# mother_v1.net
KiCad netlist of a schematic drawn in EAGLE
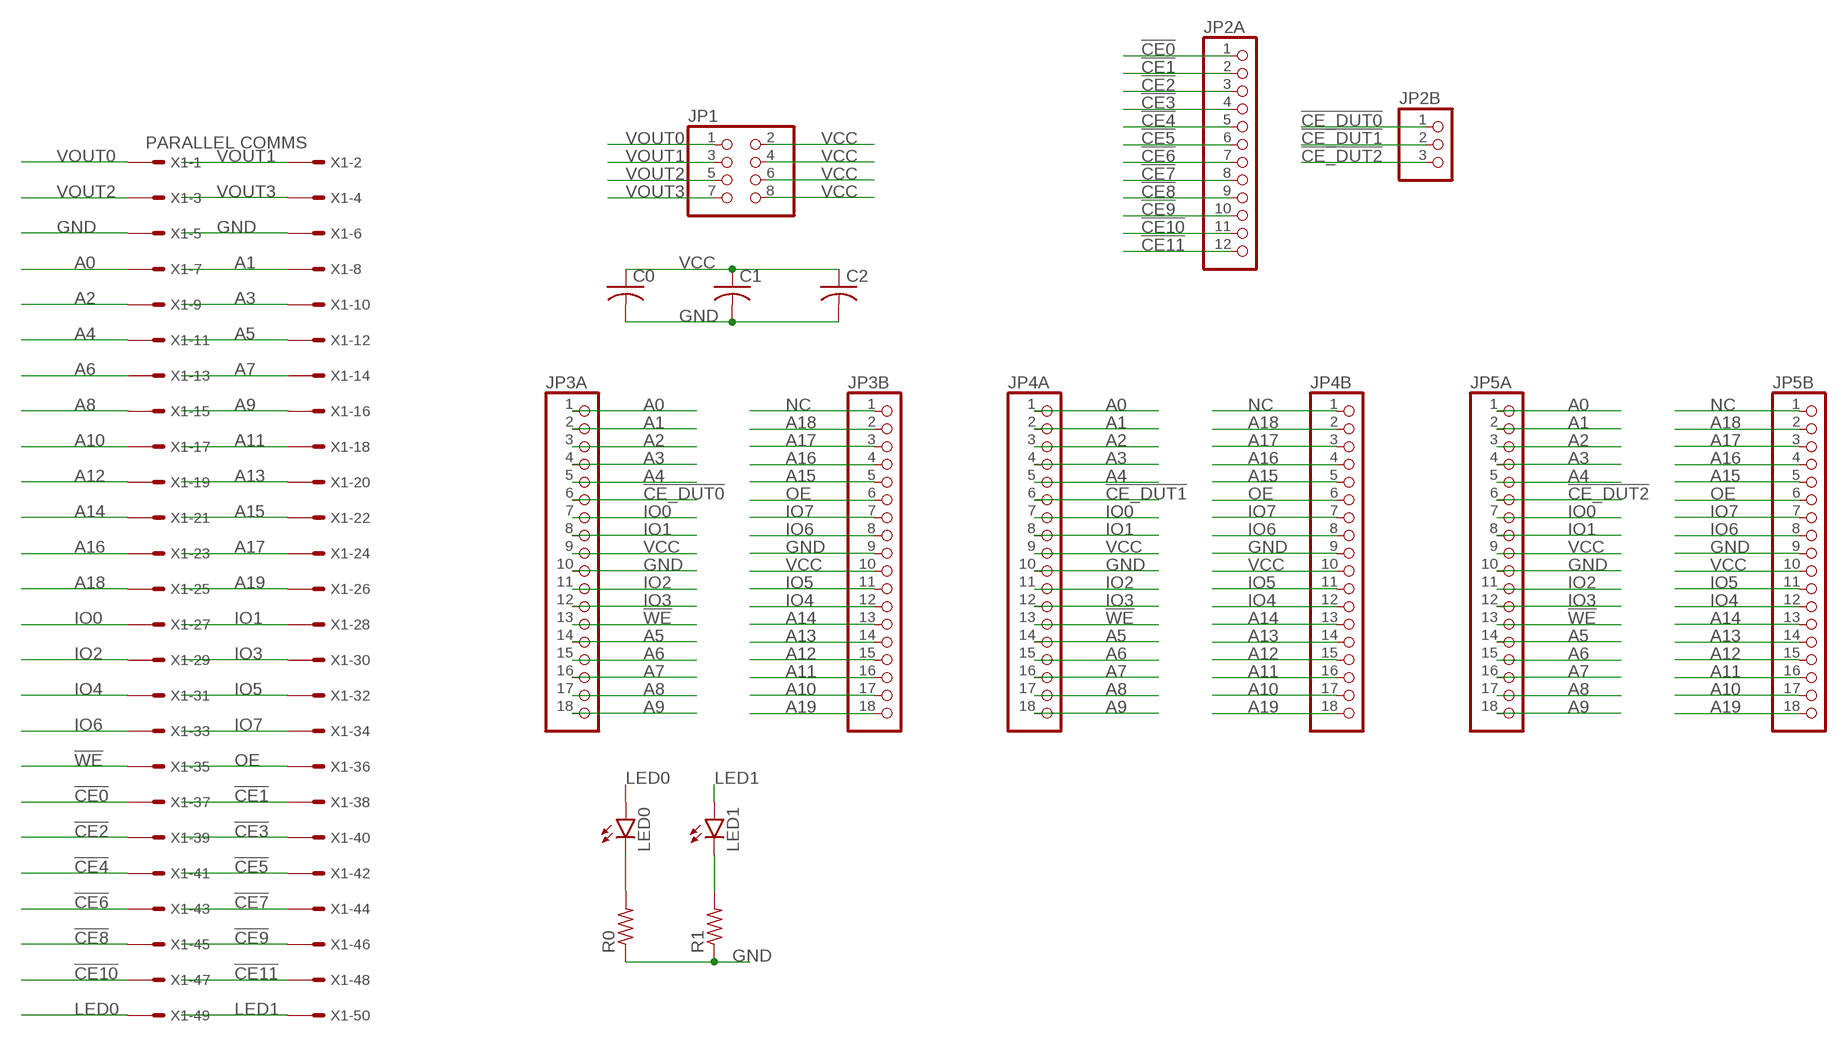
[diagram p0: schematic, sheet 1]

(export (version "E")
  (design (tool "Eeschema 10.0.6"))
  (components
    (comp (ref "C0")
      (value "C-USC0805")
      (footprint "eagle-import:C0805")
      (libsource (lib "eagle-import") (part "C-USC0805"))
    )
    (comp (ref "C1")
      (value "C-USC0805")
      (footprint "eagle-import:C0805")
      (libsource (lib "eagle-import") (part "C-USC0805"))
    )
    (comp (ref "C2")
      (value "C-USC0805")
      (footprint "eagle-import:C0805")
      (libsource (lib "eagle-import") (part "C-USC0805"))
    )
    (comp (ref "JP1")
      (value "PINHD-2X4")
      (footprint "eagle-import:2X04")
      (libsource (lib "eagle-import") (part "PINHD-2X4"))
    )
    (comp (ref "JP2A")
      (value "PINHD-1X12")
      (footprint "eagle-import:1X12")
      (libsource (lib "eagle-import") (part "PINHD-1X12"))
    )
    (comp (ref "JP2B")
      (value "PINHD-1X3")
      (footprint "eagle-import:1X03")
      (libsource (lib "eagle-import") (part "PINHD-1X3"))
    )
    (comp (ref "JP3A")
      (value "PINHD-1X18")
      (footprint "eagle-import:1X18")
      (libsource (lib "eagle-import") (part "PINHD-1X18"))
    )
    (comp (ref "JP3B")
      (value "PINHD-1X18")
      (footprint "eagle-import:1X18")
      (libsource (lib "eagle-import") (part "PINHD-1X18"))
    )
    (comp (ref "JP4A")
      (value "PINHD-1X18")
      (footprint "eagle-import:1X18")
      (libsource (lib "eagle-import") (part "PINHD-1X18"))
    )
    (comp (ref "JP4B")
      (value "PINHD-1X18")
      (footprint "eagle-import:1X18")
      (libsource (lib "eagle-import") (part "PINHD-1X18"))
    )
    (comp (ref "JP5A")
      (value "PINHD-1X18")
      (footprint "eagle-import:1X18")
      (libsource (lib "eagle-import") (part "PINHD-1X18"))
    )
    (comp (ref "JP5B")
      (value "PINHD-1X18")
      (footprint "eagle-import:1X18")
      (libsource (lib "eagle-import") (part "PINHD-1X18"))
    )
    (comp (ref "LED0")
      (value "LED3MM")
      (footprint "eagle-import:LED3MM")
      (libsource (lib "eagle-import") (part "LED3MM"))
    )
    (comp (ref "LED1")
      (value "LED3MM")
      (footprint "eagle-import:LED3MM")
      (libsource (lib "eagle-import") (part "LED3MM"))
    )
    (comp (ref "R0")
      (value "R-US_0204/7")
      (footprint "eagle-import:0204_7")
      (libsource (lib "eagle-import") (part "R-US_0204/7"))
    )
    (comp (ref "R1")
      (value "R-US_0204/7")
      (footprint "eagle-import:0204_7")
      (libsource (lib "eagle-import") (part "R-US_0204/7"))
    )
    (comp (ref "X1")
      (value "PARALLEL COMMS")
      (footprint "eagle-import:057-050-1")
      (libsource (lib "eagle-import") (part "057-050-1"))
    )
  )
  (nets
    (net (code "1") (name "/A0") (class "Default")
      (node (ref "JP3A") (pin "1") (pinfunction "1_1") (pintype "passive"))
      (node (ref "JP4A") (pin "1") (pinfunction "1_1") (pintype "passive"))
      (node (ref "JP5A") (pin "1") (pinfunction "1_1") (pintype "passive"))
      (node (ref "X1") (pin "7") (pinfunction "S_7") (pintype "passive"))
    )
    (net (code "2") (name "/A1") (class "Default")
      (node (ref "JP3A") (pin "2") (pinfunction "2_2") (pintype "passive"))
      (node (ref "JP4A") (pin "2") (pinfunction "2_2") (pintype "passive"))
      (node (ref "JP5A") (pin "2") (pinfunction "2_2") (pintype "passive"))
      (node (ref "X1") (pin "8") (pinfunction "S_8") (pintype "passive"))
    )
    (net (code "3") (name "/A2") (class "Default")
      (node (ref "JP3A") (pin "3") (pinfunction "3_3") (pintype "passive"))
      (node (ref "JP4A") (pin "3") (pinfunction "3_3") (pintype "passive"))
      (node (ref "JP5A") (pin "3") (pinfunction "3_3") (pintype "passive"))
      (node (ref "X1") (pin "9") (pinfunction "S_9") (pintype "passive"))
    )
    (net (code "4") (name "/A3") (class "Default")
      (node (ref "JP3A") (pin "4") (pinfunction "4_4") (pintype "passive"))
      (node (ref "JP4A") (pin "4") (pinfunction "4_4") (pintype "passive"))
      (node (ref "JP5A") (pin "4") (pinfunction "4_4") (pintype "passive"))
      (node (ref "X1") (pin "10") (pinfunction "S_10") (pintype "passive"))
    )
    (net (code "5") (name "/A4") (class "Default")
      (node (ref "JP3A") (pin "5") (pinfunction "5_5") (pintype "passive"))
      (node (ref "JP4A") (pin "5") (pinfunction "5_5") (pintype "passive"))
      (node (ref "JP5A") (pin "5") (pinfunction "5_5") (pintype "passive"))
      (node (ref "X1") (pin "11") (pinfunction "S_11") (pintype "passive"))
    )
    (net (code "6") (name "/A5") (class "Default")
      (node (ref "JP3A") (pin "14") (pinfunction "14_14") (pintype "passive"))
      (node (ref "JP4A") (pin "14") (pinfunction "14_14") (pintype "passive"))
      (node (ref "JP5A") (pin "14") (pinfunction "14_14") (pintype "passive"))
      (node (ref "X1") (pin "12") (pinfunction "S_12") (pintype "passive"))
    )
    (net (code "7") (name "/A6") (class "Default")
      (node (ref "JP3A") (pin "15") (pinfunction "15_15") (pintype "passive"))
      (node (ref "JP4A") (pin "15") (pinfunction "15_15") (pintype "passive"))
      (node (ref "JP5A") (pin "15") (pinfunction "15_15") (pintype "passive"))
      (node (ref "X1") (pin "13") (pinfunction "S_13") (pintype "passive"))
    )
    (net (code "8") (name "/A7") (class "Default")
      (node (ref "JP3A") (pin "16") (pinfunction "16_16") (pintype "passive"))
      (node (ref "JP4A") (pin "16") (pinfunction "16_16") (pintype "passive"))
      (node (ref "JP5A") (pin "16") (pinfunction "16_16") (pintype "passive"))
      (node (ref "X1") (pin "14") (pinfunction "S_14") (pintype "passive"))
    )
    (net (code "9") (name "/A8") (class "Default")
      (node (ref "JP3A") (pin "17") (pinfunction "17_17") (pintype "passive"))
      (node (ref "JP4A") (pin "17") (pinfunction "17_17") (pintype "passive"))
      (node (ref "JP5A") (pin "17") (pinfunction "17_17") (pintype "passive"))
      (node (ref "X1") (pin "15") (pinfunction "S_15") (pintype "passive"))
    )
    (net (code "10") (name "/A9") (class "Default")
      (node (ref "JP3A") (pin "18") (pinfunction "18_18") (pintype "passive"))
      (node (ref "JP4A") (pin "18") (pinfunction "18_18") (pintype "passive"))
      (node (ref "JP5A") (pin "18") (pinfunction "18_18") (pintype "passive"))
      (node (ref "X1") (pin "16") (pinfunction "S_16") (pintype "passive"))
    )
    (net (code "11") (name "/A10") (class "Default")
      (node (ref "JP3B") (pin "17") (pinfunction "17_17") (pintype "passive"))
      (node (ref "JP4B") (pin "17") (pinfunction "17_17") (pintype "passive"))
      (node (ref "JP5B") (pin "17") (pinfunction "17_17") (pintype "passive"))
      (node (ref "X1") (pin "17") (pinfunction "S_17") (pintype "passive"))
    )
    (net (code "12") (name "/A11") (class "Default")
      (node (ref "JP3B") (pin "16") (pinfunction "16_16") (pintype "passive"))
      (node (ref "JP4B") (pin "16") (pinfunction "16_16") (pintype "passive"))
      (node (ref "JP5B") (pin "16") (pinfunction "16_16") (pintype "passive"))
      (node (ref "X1") (pin "18") (pinfunction "S_18") (pintype "passive"))
    )
    (net (code "13") (name "/A12") (class "Default")
      (node (ref "JP3B") (pin "15") (pinfunction "15_15") (pintype "passive"))
      (node (ref "JP4B") (pin "15") (pinfunction "15_15") (pintype "passive"))
      (node (ref "JP5B") (pin "15") (pinfunction "15_15") (pintype "passive"))
      (node (ref "X1") (pin "19") (pinfunction "S_19") (pintype "passive"))
    )
    (net (code "14") (name "/A13") (class "Default")
      (node (ref "JP3B") (pin "14") (pinfunction "14_14") (pintype "passive"))
      (node (ref "JP4B") (pin "14") (pinfunction "14_14") (pintype "passive"))
      (node (ref "JP5B") (pin "14") (pinfunction "14_14") (pintype "passive"))
      (node (ref "X1") (pin "20") (pinfunction "S_20") (pintype "passive"))
    )
    (net (code "15") (name "/A14") (class "Default")
      (node (ref "JP3B") (pin "13") (pinfunction "13_13") (pintype "passive"))
      (node (ref "JP4B") (pin "13") (pinfunction "13_13") (pintype "passive"))
      (node (ref "JP5B") (pin "13") (pinfunction "13_13") (pintype "passive"))
      (node (ref "X1") (pin "21") (pinfunction "S_21") (pintype "passive"))
    )
    (net (code "16") (name "/A15") (class "Default")
      (node (ref "JP3B") (pin "5") (pinfunction "5_5") (pintype "passive"))
      (node (ref "JP4B") (pin "5") (pinfunction "5_5") (pintype "passive"))
      (node (ref "JP5B") (pin "5") (pinfunction "5_5") (pintype "passive"))
      (node (ref "X1") (pin "22") (pinfunction "S_22") (pintype "passive"))
    )
    (net (code "17") (name "/A16") (class "Default")
      (node (ref "JP3B") (pin "4") (pinfunction "4_4") (pintype "passive"))
      (node (ref "JP4B") (pin "4") (pinfunction "4_4") (pintype "passive"))
      (node (ref "JP5B") (pin "4") (pinfunction "4_4") (pintype "passive"))
      (node (ref "X1") (pin "23") (pinfunction "S_23") (pintype "passive"))
    )
    (net (code "18") (name "/A17") (class "Default")
      (node (ref "JP3B") (pin "3") (pinfunction "3_3") (pintype "passive"))
      (node (ref "JP4B") (pin "3") (pinfunction "3_3") (pintype "passive"))
      (node (ref "JP5B") (pin "3") (pinfunction "3_3") (pintype "passive"))
      (node (ref "X1") (pin "24") (pinfunction "S_24") (pintype "passive"))
    )
    (net (code "19") (name "/A18") (class "Default")
      (node (ref "JP3B") (pin "2") (pinfunction "2_2") (pintype "passive"))
      (node (ref "JP4B") (pin "2") (pinfunction "2_2") (pintype "passive"))
      (node (ref "JP5B") (pin "2") (pinfunction "2_2") (pintype "passive"))
      (node (ref "X1") (pin "25") (pinfunction "S_25") (pintype "passive"))
    )
    (net (code "20") (name "/A19") (class "Default")
      (node (ref "JP3B") (pin "18") (pinfunction "18_18") (pintype "passive"))
      (node (ref "JP4B") (pin "18") (pinfunction "18_18") (pintype "passive"))
      (node (ref "JP5B") (pin "18") (pinfunction "18_18") (pintype "passive"))
      (node (ref "X1") (pin "26") (pinfunction "S_26") (pintype "passive"))
    )
    (net (code "21") (name "/GND") (class "Default")
      (node (ref "C0") (pin "2") (pinfunction "2_2") (pintype "passive"))
      (node (ref "C1") (pin "2") (pinfunction "2_2") (pintype "passive"))
      (node (ref "C2") (pin "2") (pinfunction "2_2") (pintype "passive"))
      (node (ref "JP3A") (pin "10") (pinfunction "10_10") (pintype "passive"))
      (node (ref "JP3B") (pin "9") (pinfunction "9_9") (pintype "passive"))
      (node (ref "JP4A") (pin "10") (pinfunction "10_10") (pintype "passive"))
      (node (ref "JP4B") (pin "9") (pinfunction "9_9") (pintype "passive"))
      (node (ref "JP5A") (pin "10") (pinfunction "10_10") (pintype "passive"))
      (node (ref "JP5B") (pin "9") (pinfunction "9_9") (pintype "passive"))
      (node (ref "R0") (pin "1") (pinfunction "1_1") (pintype "passive"))
      (node (ref "R1") (pin "1") (pinfunction "1_1") (pintype "passive"))
      (node (ref "X1") (pin "5") (pinfunction "S_5") (pintype "passive"))
      (node (ref "X1") (pin "6") (pinfunction "S_6") (pintype "passive"))
    )
    (net (code "22") (name "/IO0") (class "Default")
      (node (ref "JP3A") (pin "7") (pinfunction "7_7") (pintype "passive"))
      (node (ref "JP4A") (pin "7") (pinfunction "7_7") (pintype "passive"))
      (node (ref "JP5A") (pin "7") (pinfunction "7_7") (pintype "passive"))
      (node (ref "X1") (pin "27") (pinfunction "S_27") (pintype "passive"))
    )
    (net (code "23") (name "/IO1") (class "Default")
      (node (ref "JP3A") (pin "8") (pinfunction "8_8") (pintype "passive"))
      (node (ref "JP4A") (pin "8") (pinfunction "8_8") (pintype "passive"))
      (node (ref "JP5A") (pin "8") (pinfunction "8_8") (pintype "passive"))
      (node (ref "X1") (pin "28") (pinfunction "S_28") (pintype "passive"))
    )
    (net (code "24") (name "/IO2") (class "Default")
      (node (ref "JP3A") (pin "11") (pinfunction "11_11") (pintype "passive"))
      (node (ref "JP4A") (pin "11") (pinfunction "11_11") (pintype "passive"))
      (node (ref "JP5A") (pin "11") (pinfunction "11_11") (pintype "passive"))
      (node (ref "X1") (pin "29") (pinfunction "S_29") (pintype "passive"))
    )
    (net (code "25") (name "/IO3") (class "Default")
      (node (ref "JP3A") (pin "12") (pinfunction "12_12") (pintype "passive"))
      (node (ref "JP4A") (pin "12") (pinfunction "12_12") (pintype "passive"))
      (node (ref "JP5A") (pin "12") (pinfunction "12_12") (pintype "passive"))
      (node (ref "X1") (pin "30") (pinfunction "S_30") (pintype "passive"))
    )
    (net (code "26") (name "/IO4") (class "Default")
      (node (ref "JP3B") (pin "12") (pinfunction "12_12") (pintype "passive"))
      (node (ref "JP4B") (pin "12") (pinfunction "12_12") (pintype "passive"))
      (node (ref "JP5B") (pin "12") (pinfunction "12_12") (pintype "passive"))
      (node (ref "X1") (pin "31") (pinfunction "S_31") (pintype "passive"))
    )
    (net (code "27") (name "/IO5") (class "Default")
      (node (ref "JP3B") (pin "11") (pinfunction "11_11") (pintype "passive"))
      (node (ref "JP4B") (pin "11") (pinfunction "11_11") (pintype "passive"))
      (node (ref "JP5B") (pin "11") (pinfunction "11_11") (pintype "passive"))
      (node (ref "X1") (pin "32") (pinfunction "S_32") (pintype "passive"))
    )
    (net (code "28") (name "/IO6") (class "Default")
      (node (ref "JP3B") (pin "8") (pinfunction "8_8") (pintype "passive"))
      (node (ref "JP4B") (pin "8") (pinfunction "8_8") (pintype "passive"))
      (node (ref "JP5B") (pin "8") (pinfunction "8_8") (pintype "passive"))
      (node (ref "X1") (pin "33") (pinfunction "S_33") (pintype "passive"))
    )
    (net (code "29") (name "/IO7") (class "Default")
      (node (ref "JP3B") (pin "7") (pinfunction "7_7") (pintype "passive"))
      (node (ref "JP4B") (pin "7") (pinfunction "7_7") (pintype "passive"))
      (node (ref "JP5B") (pin "7") (pinfunction "7_7") (pintype "passive"))
      (node (ref "X1") (pin "34") (pinfunction "S_34") (pintype "passive"))
    )
    (net (code "30") (name "/LED0") (class "Default")
      (node (ref "LED0") (pin "A") (pinfunction "A_A") (pintype "passive"))
      (node (ref "X1") (pin "49") (pinfunction "S_49") (pintype "passive"))
    )
    (net (code "31") (name "/LED1") (class "Default")
      (node (ref "LED1") (pin "A") (pinfunction "A_A") (pintype "passive"))
      (node (ref "X1") (pin "50") (pinfunction "S_50") (pintype "passive"))
    )
    (net (code "32") (name "/NC") (class "Default")
      (node (ref "JP3B") (pin "1") (pinfunction "1_1") (pintype "passive"))
      (node (ref "JP4B") (pin "1") (pinfunction "1_1") (pintype "passive"))
      (node (ref "JP5B") (pin "1") (pinfunction "1_1") (pintype "passive"))
    )
    (net (code "33") (name "/OE") (class "Default")
      (node (ref "JP3B") (pin "6") (pinfunction "6_6") (pintype "passive"))
      (node (ref "JP4B") (pin "6") (pinfunction "6_6") (pintype "passive"))
      (node (ref "JP5B") (pin "6") (pinfunction "6_6") (pintype "passive"))
      (node (ref "X1") (pin "36") (pinfunction "S_36") (pintype "passive"))
    )
    (net (code "34") (name "/VCC") (class "Default")
      (node (ref "C0") (pin "1") (pinfunction "1_1") (pintype "passive"))
      (node (ref "C1") (pin "1") (pinfunction "1_1") (pintype "passive"))
      (node (ref "C2") (pin "1") (pinfunction "1_1") (pintype "passive"))
      (node (ref "JP1") (pin "2") (pinfunction "2_2") (pintype "passive"))
      (node (ref "JP1") (pin "4") (pinfunction "4_4") (pintype "passive"))
      (node (ref "JP1") (pin "6") (pinfunction "6_6") (pintype "passive"))
      (node (ref "JP1") (pin "8") (pinfunction "8_8") (pintype "passive"))
      (node (ref "JP3A") (pin "9") (pinfunction "9_9") (pintype "passive"))
      (node (ref "JP3B") (pin "10") (pinfunction "10_10") (pintype "passive"))
      (node (ref "JP4A") (pin "9") (pinfunction "9_9") (pintype "passive"))
      (node (ref "JP4B") (pin "10") (pinfunction "10_10") (pintype "passive"))
      (node (ref "JP5A") (pin "9") (pinfunction "9_9") (pintype "passive"))
      (node (ref "JP5B") (pin "10") (pinfunction "10_10") (pintype "passive"))
    )
    (net (code "35") (name "/VOUT0") (class "Default")
      (node (ref "JP1") (pin "1") (pinfunction "1_1") (pintype "passive"))
      (node (ref "X1") (pin "1") (pinfunction "S_1") (pintype "passive"))
    )
    (net (code "36") (name "/VOUT1") (class "Default")
      (node (ref "JP1") (pin "3") (pinfunction "3_3") (pintype "passive"))
      (node (ref "X1") (pin "2") (pinfunction "S_2") (pintype "passive"))
    )
    (net (code "37") (name "/VOUT2") (class "Default")
      (node (ref "JP1") (pin "5") (pinfunction "5_5") (pintype "passive"))
      (node (ref "X1") (pin "3") (pinfunction "S_3") (pintype "passive"))
    )
    (net (code "38") (name "/VOUT3") (class "Default")
      (node (ref "JP1") (pin "7") (pinfunction "7_7") (pintype "passive"))
      (node (ref "X1") (pin "4") (pinfunction "S_4") (pintype "passive"))
    )
    (net (code "39") (name "/~{CE0}") (class "Default")
      (node (ref "JP2A") (pin "1") (pinfunction "1_1") (pintype "passive"))
      (node (ref "X1") (pin "37") (pinfunction "S_37") (pintype "passive"))
    )
    (net (code "40") (name "/~{CE1}") (class "Default")
      (node (ref "JP2A") (pin "2") (pinfunction "2_2") (pintype "passive"))
      (node (ref "X1") (pin "38") (pinfunction "S_38") (pintype "passive"))
    )
    (net (code "41") (name "/~{CE2}") (class "Default")
      (node (ref "JP2A") (pin "3") (pinfunction "3_3") (pintype "passive"))
      (node (ref "X1") (pin "39") (pinfunction "S_39") (pintype "passive"))
    )
    (net (code "42") (name "/~{CE3}") (class "Default")
      (node (ref "JP2A") (pin "4") (pinfunction "4_4") (pintype "passive"))
      (node (ref "X1") (pin "40") (pinfunction "S_40") (pintype "passive"))
    )
    (net (code "43") (name "/~{CE4}") (class "Default")
      (node (ref "JP2A") (pin "5") (pinfunction "5_5") (pintype "passive"))
      (node (ref "X1") (pin "41") (pinfunction "S_41") (pintype "passive"))
    )
    (net (code "44") (name "/~{CE5}") (class "Default")
      (node (ref "JP2A") (pin "6") (pinfunction "6_6") (pintype "passive"))
      (node (ref "X1") (pin "42") (pinfunction "S_42") (pintype "passive"))
    )
    (net (code "45") (name "/~{CE6}") (class "Default")
      (node (ref "JP2A") (pin "7") (pinfunction "7_7") (pintype "passive"))
      (node (ref "X1") (pin "43") (pinfunction "S_43") (pintype "passive"))
    )
    (net (code "46") (name "/~{CE7}") (class "Default")
      (node (ref "JP2A") (pin "8") (pinfunction "8_8") (pintype "passive"))
      (node (ref "X1") (pin "44") (pinfunction "S_44") (pintype "passive"))
    )
    (net (code "47") (name "/~{CE8}") (class "Default")
      (node (ref "JP2A") (pin "9") (pinfunction "9_9") (pintype "passive"))
      (node (ref "X1") (pin "45") (pinfunction "S_45") (pintype "passive"))
    )
    (net (code "48") (name "/~{CE9}") (class "Default")
      (node (ref "JP2A") (pin "10") (pinfunction "10_10") (pintype "passive"))
      (node (ref "X1") (pin "46") (pinfunction "S_46") (pintype "passive"))
    )
    (net (code "49") (name "/~{CE10}") (class "Default")
      (node (ref "JP2A") (pin "11") (pinfunction "11_11") (pintype "passive"))
      (node (ref "X1") (pin "47") (pinfunction "S_47") (pintype "passive"))
    )
    (net (code "50") (name "/~{CE11}") (class "Default")
      (node (ref "JP2A") (pin "12") (pinfunction "12_12") (pintype "passive"))
      (node (ref "X1") (pin "48") (pinfunction "S_48") (pintype "passive"))
    )
    (net (code "51") (name "/~{CE_DUT0}") (class "Default")
      (node (ref "JP2B") (pin "1") (pinfunction "1_1") (pintype "passive"))
      (node (ref "JP3A") (pin "6") (pinfunction "6_6") (pintype "passive"))
    )
    (net (code "52") (name "/~{CE_DUT1}") (class "Default")
      (node (ref "JP2B") (pin "2") (pinfunction "2_2") (pintype "passive"))
      (node (ref "JP4A") (pin "6") (pinfunction "6_6") (pintype "passive"))
    )
    (net (code "53") (name "/~{CE_DUT2}") (class "Default")
      (node (ref "JP2B") (pin "3") (pinfunction "3_3") (pintype "passive"))
      (node (ref "JP5A") (pin "6") (pinfunction "6_6") (pintype "passive"))
    )
    (net (code "54") (name "/~{WE}") (class "Default")
      (node (ref "JP3A") (pin "13") (pinfunction "13_13") (pintype "passive"))
      (node (ref "JP4A") (pin "13") (pinfunction "13_13") (pintype "passive"))
      (node (ref "JP5A") (pin "13") (pinfunction "13_13") (pintype "passive"))
      (node (ref "X1") (pin "35") (pinfunction "S_35") (pintype "passive"))
    )
    (net (code "55") (name "Net-(LED0-C)") (class "Default")
      (node (ref "LED0") (pin "K") (pinfunction "C_K") (pintype "passive"))
      (node (ref "R0") (pin "2") (pinfunction "2_2") (pintype "passive"))
    )
    (net (code "56") (name "Net-(LED1-C)") (class "Default")
      (node (ref "LED1") (pin "K") (pinfunction "C_K") (pintype "passive"))
      (node (ref "R1") (pin "2") (pinfunction "2_2") (pintype "passive"))
    )
  )
)
